# TopLevel.net
KiCad netlist of a schematic drawn in Altium Designer
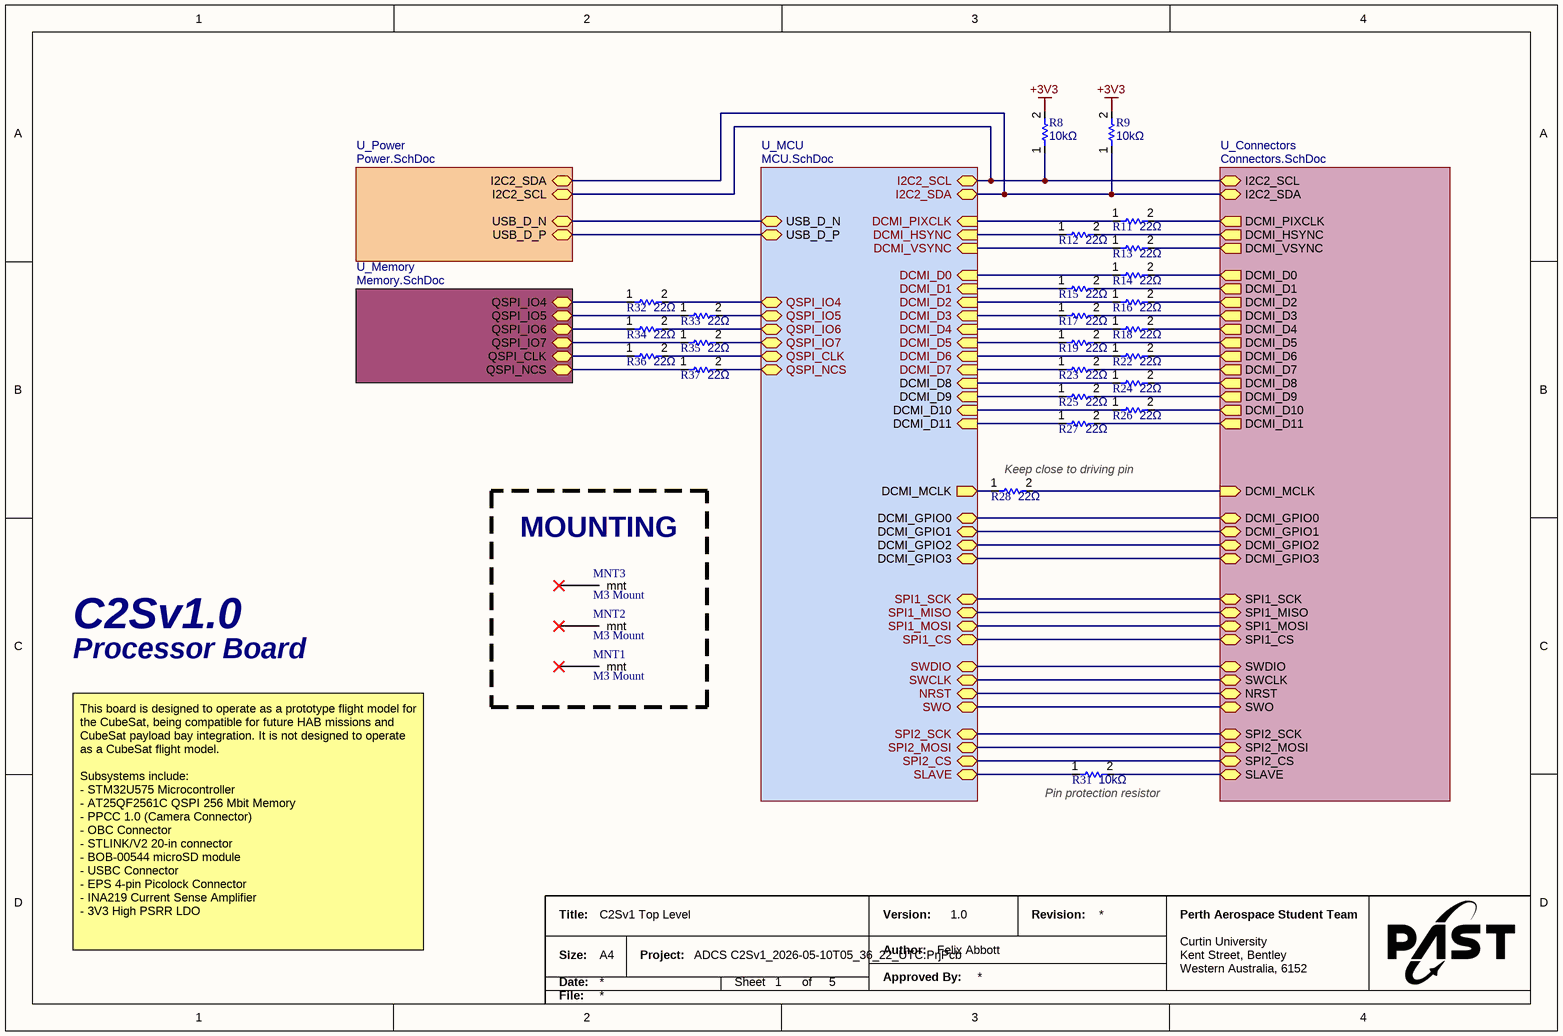
[diagram p0: TopLevel.SchDoc]

(export (version "E")
  (design (tool "Eeschema 10.0.6"))
  (components
    (comp (ref "MNT1")
      (value "M3 Mount")
      (footprint "M3_Mount-Footprint-1")
      (description "M3 mounting hole")
      (fields (field (name "AUTHOR") "Raphael Ho"))
      (libsource (lib "Perth Aerospace Student Team") (part "M3_Mount-Symbol-1"))
    )
    (comp (ref "MNT2")
      (value "M3 Mount")
      (footprint "M3_Mount-Footprint-1")
      (description "M3 mounting hole")
      (fields (field (name "AUTHOR") "Raphael Ho"))
      (libsource (lib "Perth Aerospace Student Team") (part "M3_Mount-Symbol-1"))
    )
    (comp (ref "MNT3")
      (value "M3 Mount")
      (footprint "M3_Mount-Footprint-1")
      (description "M3 mounting hole")
      (fields (field (name "AUTHOR") "Raphael Ho"))
      (libsource (lib "Perth Aerospace Student Team") (part "M3_Mount-Symbol-1"))
    )
    (comp (ref "R8")
      (value "10kΩ")
      (footprint "FP-CRCW0603-e3-IPC_C")
      (description "Resistor")
      (fields
        (field (name "TOLERANCE") "1%")
        (field (name "Comment") "CRCW060310K0FKED")
        (field (name "ADDED BY") "Felix")
      )
      (libsource (lib "") (part "1029c3af85768c4190bb7ad29bc67b5_1"))
    )
    (comp (ref "R9")
      (value "10kΩ")
      (footprint "FP-CRCW0603-e3-IPC_C")
      (description "Resistor")
      (fields
        (field (name "TOLERANCE") "1%")
        (field (name "Comment") "CRCW060310K0FKED")
        (field (name "ADDED BY") "Felix")
      )
      (libsource (lib "") (part "1029c3af85768c4190bb7ad29bc67b5_1"))
    )
    (comp (ref "R11")
      (value "22Ω")
      (footprint "FP-CRCW0402-e3-IPC_A")
      (description "Resistor")
      (fields
        (field (name "TOLERANCE") "5%")
        (field (name "Comment") "CRCW040222R0JNED")
        (field (name "ADDED BY") "Felix Abbott")
      )
      (libsource (lib "Perth Aerospace Student Team") (part "1029c3af85768c4190bb7ad29bc67b5"))
    )
    (comp (ref "R12")
      (value "22Ω")
      (footprint "FP-CRCW0402-e3-IPC_A")
      (description "Resistor")
      (fields
        (field (name "TOLERANCE") "5%")
        (field (name "Comment") "CRCW040222R0JNED")
        (field (name "ADDED BY") "Felix Abbott")
      )
      (libsource (lib "Perth Aerospace Student Team") (part "1029c3af85768c4190bb7ad29bc67b5"))
    )
    (comp (ref "R13")
      (value "22Ω")
      (footprint "FP-CRCW0402-e3-IPC_A")
      (description "Resistor")
      (fields
        (field (name "TOLERANCE") "5%")
        (field (name "Comment") "CRCW040222R0JNED")
        (field (name "ADDED BY") "Felix Abbott")
      )
      (libsource (lib "Perth Aerospace Student Team") (part "1029c3af85768c4190bb7ad29bc67b5"))
    )
    (comp (ref "R14")
      (value "22Ω")
      (footprint "FP-CRCW0402-e3-IPC_A")
      (description "Resistor")
      (fields
        (field (name "TOLERANCE") "5%")
        (field (name "Comment") "CRCW040222R0JNED")
        (field (name "ADDED BY") "Felix Abbott")
      )
      (libsource (lib "Perth Aerospace Student Team") (part "1029c3af85768c4190bb7ad29bc67b5"))
    )
    (comp (ref "R15")
      (value "22Ω")
      (footprint "FP-CRCW0402-e3-IPC_A")
      (description "Resistor")
      (fields
        (field (name "TOLERANCE") "5%")
        (field (name "Comment") "CRCW040222R0JNED")
        (field (name "ADDED BY") "Felix Abbott")
      )
      (libsource (lib "Perth Aerospace Student Team") (part "1029c3af85768c4190bb7ad29bc67b5"))
    )
    (comp (ref "R16")
      (value "22Ω")
      (footprint "FP-CRCW0402-e3-IPC_A")
      (description "Resistor")
      (fields
        (field (name "TOLERANCE") "5%")
        (field (name "Comment") "CRCW040222R0JNED")
        (field (name "ADDED BY") "Felix Abbott")
      )
      (libsource (lib "Perth Aerospace Student Team") (part "1029c3af85768c4190bb7ad29bc67b5"))
    )
    (comp (ref "R17")
      (value "22Ω")
      (footprint "FP-CRCW0402-e3-IPC_A")
      (description "Resistor")
      (fields
        (field (name "TOLERANCE") "5%")
        (field (name "Comment") "CRCW040222R0JNED")
        (field (name "ADDED BY") "Felix Abbott")
      )
      (libsource (lib "Perth Aerospace Student Team") (part "1029c3af85768c4190bb7ad29bc67b5"))
    )
    (comp (ref "R18")
      (value "22Ω")
      (footprint "FP-CRCW0402-e3-IPC_A")
      (description "Resistor")
      (fields
        (field (name "TOLERANCE") "5%")
        (field (name "Comment") "CRCW040222R0JNED")
        (field (name "ADDED BY") "Felix Abbott")
      )
      (libsource (lib "Perth Aerospace Student Team") (part "1029c3af85768c4190bb7ad29bc67b5"))
    )
    (comp (ref "R19")
      (value "22Ω")
      (footprint "FP-CRCW0402-e3-IPC_A")
      (description "Resistor")
      (fields
        (field (name "TOLERANCE") "5%")
        (field (name "Comment") "CRCW040222R0JNED")
        (field (name "ADDED BY") "Felix Abbott")
      )
      (libsource (lib "Perth Aerospace Student Team") (part "1029c3af85768c4190bb7ad29bc67b5"))
    )
    (comp (ref "R22")
      (value "22Ω")
      (footprint "FP-CRCW0402-e3-IPC_A")
      (description "Resistor")
      (fields
        (field (name "TOLERANCE") "5%")
        (field (name "Comment") "CRCW040222R0JNED")
        (field (name "ADDED BY") "Felix Abbott")
      )
      (libsource (lib "Perth Aerospace Student Team") (part "1029c3af85768c4190bb7ad29bc67b5"))
    )
    (comp (ref "R23")
      (value "22Ω")
      (footprint "FP-CRCW0402-e3-IPC_A")
      (description "Resistor")
      (fields
        (field (name "TOLERANCE") "5%")
        (field (name "Comment") "CRCW040222R0JNED")
        (field (name "ADDED BY") "Felix Abbott")
      )
      (libsource (lib "Perth Aerospace Student Team") (part "1029c3af85768c4190bb7ad29bc67b5"))
    )
    (comp (ref "R24")
      (value "22Ω")
      (footprint "FP-CRCW0402-e3-IPC_A")
      (description "Resistor")
      (fields
        (field (name "TOLERANCE") "5%")
        (field (name "Comment") "CRCW040222R0JNED")
        (field (name "ADDED BY") "Felix Abbott")
      )
      (libsource (lib "Perth Aerospace Student Team") (part "1029c3af85768c4190bb7ad29bc67b5"))
    )
    (comp (ref "R25")
      (value "22Ω")
      (footprint "FP-CRCW0402-e3-IPC_A")
      (description "Resistor")
      (fields
        (field (name "TOLERANCE") "5%")
        (field (name "Comment") "CRCW040222R0JNED")
        (field (name "ADDED BY") "Felix Abbott")
      )
      (libsource (lib "Perth Aerospace Student Team") (part "1029c3af85768c4190bb7ad29bc67b5"))
    )
    (comp (ref "R26")
      (value "22Ω")
      (footprint "FP-CRCW0402-e3-IPC_A")
      (description "Resistor")
      (fields
        (field (name "TOLERANCE") "5%")
        (field (name "Comment") "CRCW040222R0JNED")
        (field (name "ADDED BY") "Felix Abbott")
      )
      (libsource (lib "Perth Aerospace Student Team") (part "1029c3af85768c4190bb7ad29bc67b5"))
    )
    (comp (ref "R27")
      (value "22Ω")
      (footprint "FP-CRCW0402-e3-IPC_A")
      (description "Resistor")
      (fields
        (field (name "TOLERANCE") "5%")
        (field (name "Comment") "CRCW040222R0JNED")
        (field (name "ADDED BY") "Felix Abbott")
      )
      (libsource (lib "Perth Aerospace Student Team") (part "1029c3af85768c4190bb7ad29bc67b5"))
    )
    (comp (ref "R28")
      (value "22Ω")
      (footprint "FP-CRCW0402-e3-IPC_A")
      (description "Resistor")
      (fields
        (field (name "TOLERANCE") "5%")
        (field (name "Comment") "CRCW040222R0JNED")
        (field (name "ADDED BY") "Felix Abbott")
      )
      (libsource (lib "Perth Aerospace Student Team") (part "1029c3af85768c4190bb7ad29bc67b5"))
    )
    (comp (ref "R31")
      (value "10kΩ")
      (footprint "FP-CRCW0603-e3-IPC_C")
      (description "Resistor")
      (fields
        (field (name "TOLERANCE") "1%")
        (field (name "Comment") "CRCW060310K0FKED")
        (field (name "ADDED BY") "Felix")
      )
      (libsource (lib "") (part "1029c3af85768c4190bb7ad29bc67b5_1"))
    )
    (comp (ref "R32")
      (value "22Ω")
      (footprint "FP-CRCW0402-e3-IPC_A")
      (description "Resistor")
      (fields
        (field (name "TOLERANCE") "5%")
        (field (name "Comment") "CRCW040222R0JNED")
        (field (name "ADDED BY") "Felix Abbott")
      )
      (libsource (lib "Perth Aerospace Student Team") (part "1029c3af85768c4190bb7ad29bc67b5"))
    )
    (comp (ref "R33")
      (value "22Ω")
      (footprint "FP-CRCW0402-e3-IPC_A")
      (description "Resistor")
      (fields
        (field (name "TOLERANCE") "5%")
        (field (name "Comment") "CRCW040222R0JNED")
        (field (name "ADDED BY") "Felix Abbott")
      )
      (libsource (lib "Perth Aerospace Student Team") (part "1029c3af85768c4190bb7ad29bc67b5"))
    )
    (comp (ref "R34")
      (value "22Ω")
      (footprint "FP-CRCW0402-e3-IPC_A")
      (description "Resistor")
      (fields
        (field (name "TOLERANCE") "5%")
        (field (name "Comment") "CRCW040222R0JNED")
        (field (name "ADDED BY") "Felix Abbott")
      )
      (libsource (lib "Perth Aerospace Student Team") (part "1029c3af85768c4190bb7ad29bc67b5"))
    )
    (comp (ref "R35")
      (value "22Ω")
      (footprint "FP-CRCW0402-e3-IPC_A")
      (description "Resistor")
      (fields
        (field (name "TOLERANCE") "5%")
        (field (name "Comment") "CRCW040222R0JNED")
        (field (name "ADDED BY") "Felix Abbott")
      )
      (libsource (lib "Perth Aerospace Student Team") (part "1029c3af85768c4190bb7ad29bc67b5"))
    )
    (comp (ref "R36")
      (value "22Ω")
      (footprint "FP-CRCW0402-e3-IPC_A")
      (description "Resistor")
      (fields
        (field (name "TOLERANCE") "5%")
        (field (name "Comment") "CRCW040222R0JNED")
        (field (name "ADDED BY") "Felix Abbott")
      )
      (libsource (lib "Perth Aerospace Student Team") (part "1029c3af85768c4190bb7ad29bc67b5"))
    )
    (comp (ref "R37")
      (value "22Ω")
      (footprint "FP-CRCW0402-e3-IPC_A")
      (description "Resistor")
      (fields
        (field (name "TOLERANCE") "5%")
        (field (name "Comment") "CRCW040222R0JNED")
        (field (name "ADDED BY") "Felix Abbott")
      )
      (libsource (lib "Perth Aerospace Student Team") (part "1029c3af85768c4190bb7ad29bc67b5"))
    )
  )
  (nets
    (net (code "1") (name "+3V3") (class "Default")
      (node (ref "R8") (pin "2") (pinfunction "2_2") (pintype "passive"))
      (node (ref "R9") (pin "2") (pinfunction "2_2") (pintype "passive"))
    )
    (net (code "2") (name "/DCMI_D0") (class "Default")
      (node (ref "R14") (pin "1") (pinfunction "1_1") (pintype "passive"))
    )
    (net (code "3") (name "/DCMI_D0_1") (class "Default")
      (node (ref "R14") (pin "2") (pinfunction "2_2") (pintype "passive"))
    )
    (net (code "4") (name "/DCMI_D1") (class "Default")
      (node (ref "R15") (pin "1") (pinfunction "1_1") (pintype "passive"))
    )
    (net (code "5") (name "/DCMI_D1_1") (class "Default")
      (node (ref "R15") (pin "2") (pinfunction "2_2") (pintype "passive"))
    )
    (net (code "6") (name "/DCMI_D2") (class "Default")
      (node (ref "R16") (pin "1") (pinfunction "1_1") (pintype "passive"))
    )
    (net (code "7") (name "/DCMI_D2_1") (class "Default")
      (node (ref "R16") (pin "2") (pinfunction "2_2") (pintype "passive"))
    )
    (net (code "8") (name "/DCMI_D3") (class "Default")
      (node (ref "R17") (pin "1") (pinfunction "1_1") (pintype "passive"))
    )
    (net (code "9") (name "/DCMI_D3_1") (class "Default")
      (node (ref "R17") (pin "2") (pinfunction "2_2") (pintype "passive"))
    )
    (net (code "10") (name "/DCMI_D4") (class "Default")
      (node (ref "R18") (pin "2") (pinfunction "2_2") (pintype "passive"))
    )
    (net (code "11") (name "/DCMI_D4_1") (class "Default")
      (node (ref "R18") (pin "1") (pinfunction "1_1") (pintype "passive"))
    )
    (net (code "12") (name "/DCMI_D5") (class "Default")
      (node (ref "R19") (pin "1") (pinfunction "1_1") (pintype "passive"))
    )
    (net (code "13") (name "/DCMI_D5_1") (class "Default")
      (node (ref "R19") (pin "2") (pinfunction "2_2") (pintype "passive"))
    )
    (net (code "14") (name "/DCMI_D6") (class "Default")
      (node (ref "R22") (pin "2") (pinfunction "2_2") (pintype "passive"))
    )
    (net (code "15") (name "/DCMI_D6_1") (class "Default")
      (node (ref "R22") (pin "1") (pinfunction "1_1") (pintype "passive"))
    )
    (net (code "16") (name "/DCMI_D7") (class "Default")
      (node (ref "R23") (pin "2") (pinfunction "2_2") (pintype "passive"))
    )
    (net (code "17") (name "/DCMI_D7_1") (class "Default")
      (node (ref "R23") (pin "1") (pinfunction "1_1") (pintype "passive"))
    )
    (net (code "18") (name "/DCMI_D8") (class "Default")
      (node (ref "R24") (pin "2") (pinfunction "2_2") (pintype "passive"))
    )
    (net (code "19") (name "/DCMI_D8_1") (class "Default")
      (node (ref "R24") (pin "1") (pinfunction "1_1") (pintype "passive"))
    )
    (net (code "20") (name "/DCMI_D9") (class "Default")
      (node (ref "R25") (pin "2") (pinfunction "2_2") (pintype "passive"))
    )
    (net (code "21") (name "/DCMI_D9_1") (class "Default")
      (node (ref "R25") (pin "1") (pinfunction "1_1") (pintype "passive"))
    )
    (net (code "22") (name "/DCMI_D10") (class "Default")
      (node (ref "R26") (pin "2") (pinfunction "2_2") (pintype "passive"))
    )
    (net (code "23") (name "/DCMI_D10_1") (class "Default")
      (node (ref "R26") (pin "1") (pinfunction "1_1") (pintype "passive"))
    )
    (net (code "24") (name "/DCMI_D11") (class "Default")
      (node (ref "R27") (pin "1") (pinfunction "1_1") (pintype "passive"))
    )
    (net (code "25") (name "/DCMI_D11_1") (class "Default")
      (node (ref "R27") (pin "2") (pinfunction "2_2") (pintype "passive"))
    )
    (net (code "30") (name "/DCMI_HSYNC") (class "Default")
      (node (ref "R12") (pin "1") (pinfunction "1_1") (pintype "passive"))
    )
    (net (code "31") (name "/DCMI_HSYNC_1") (class "Default")
      (node (ref "R12") (pin "2") (pinfunction "2_2") (pintype "passive"))
    )
    (net (code "32") (name "/DCMI_MCLK") (class "Default")
      (node (ref "R28") (pin "1") (pinfunction "1_1") (pintype "passive"))
    )
    (net (code "33") (name "/DCMI_MCLK_1") (class "Default")
      (node (ref "R28") (pin "2") (pinfunction "2_2") (pintype "passive"))
    )
    (net (code "34") (name "/DCMI_PIXCLK") (class "Default")
      (node (ref "R11") (pin "1") (pinfunction "1_1") (pintype "passive"))
    )
    (net (code "35") (name "/DCMI_PIXCLK_1") (class "Default")
      (node (ref "R11") (pin "2") (pinfunction "2_2") (pintype "passive"))
    )
    (net (code "36") (name "/DCMI_VSYNC") (class "Default")
      (node (ref "R13") (pin "1") (pinfunction "1_1") (pintype "passive"))
    )
    (net (code "37") (name "/DCMI_VSYNC_1") (class "Default")
      (node (ref "R13") (pin "2") (pinfunction "2_2") (pintype "passive"))
    )
    (net (code "38") (name "/I2C2_SCL") (class "Default")
      (node (ref "R8") (pin "1") (pinfunction "1_1") (pintype "passive"))
    )
    (net (code "39") (name "/I2C2_SDA") (class "Default")
      (node (ref "R9") (pin "1") (pinfunction "1_1") (pintype "passive"))
    )
    (net (code "41") (name "/QSPI_CLK") (class "Default")
      (node (ref "R36") (pin "2") (pinfunction "2_2") (pintype "passive"))
    )
    (net (code "42") (name "/QSPI_CLK_1") (class "Default")
      (node (ref "R36") (pin "1") (pinfunction "1_1") (pintype "passive"))
    )
    (net (code "43") (name "/QSPI_IO4") (class "Default")
      (node (ref "R32") (pin "1") (pinfunction "1_1") (pintype "passive"))
    )
    (net (code "44") (name "/QSPI_IO4_1") (class "Default")
      (node (ref "R32") (pin "2") (pinfunction "2_2") (pintype "passive"))
    )
    (net (code "45") (name "/QSPI_IO5") (class "Default")
      (node (ref "R33") (pin "2") (pinfunction "2_2") (pintype "passive"))
    )
    (net (code "46") (name "/QSPI_IO5_1") (class "Default")
      (node (ref "R33") (pin "1") (pinfunction "1_1") (pintype "passive"))
    )
    (net (code "47") (name "/QSPI_IO6") (class "Default")
      (node (ref "R34") (pin "2") (pinfunction "2_2") (pintype "passive"))
    )
    (net (code "48") (name "/QSPI_IO6_1") (class "Default")
      (node (ref "R34") (pin "1") (pinfunction "1_1") (pintype "passive"))
    )
    (net (code "49") (name "/QSPI_IO7") (class "Default")
      (node (ref "R35") (pin "2") (pinfunction "2_2") (pintype "passive"))
    )
    (net (code "50") (name "/QSPI_IO7_1") (class "Default")
      (node (ref "R35") (pin "1") (pinfunction "1_1") (pintype "passive"))
    )
    (net (code "51") (name "/QSPI_NCS") (class "Default")
      (node (ref "R37") (pin "2") (pinfunction "2_2") (pintype "passive"))
    )
    (net (code "52") (name "/QSPI_NCS_1") (class "Default")
      (node (ref "R37") (pin "1") (pinfunction "1_1") (pintype "passive"))
    )
    (net (code "53") (name "/SLAVE") (class "Default")
      (node (ref "R31") (pin "2") (pinfunction "2_2") (pintype "passive"))
    )
    (net (code "54") (name "/SLAVE_1") (class "Default")
      (node (ref "R31") (pin "1") (pinfunction "1_1") (pintype "passive"))
    )
    (net (code "67") (name "unconnected-(MNT1-mnt-Pad1)") (class "Default")
      (node (ref "MNT1") (pin "1") (pinfunction "mnt_1") (pintype "passive+no_connect"))
    )
    (net (code "68") (name "unconnected-(MNT2-mnt-Pad1)") (class "Default")
      (node (ref "MNT2") (pin "1") (pinfunction "mnt_1") (pintype "passive+no_connect"))
    )
    (net (code "69") (name "unconnected-(MNT3-mnt-Pad1)") (class "Default")
      (node (ref "MNT3") (pin "1") (pinfunction "mnt_1") (pintype "passive+no_connect"))
    )
  )
)
